# QIF.net
KiCad netlist of a schematic drawn in EAGLE
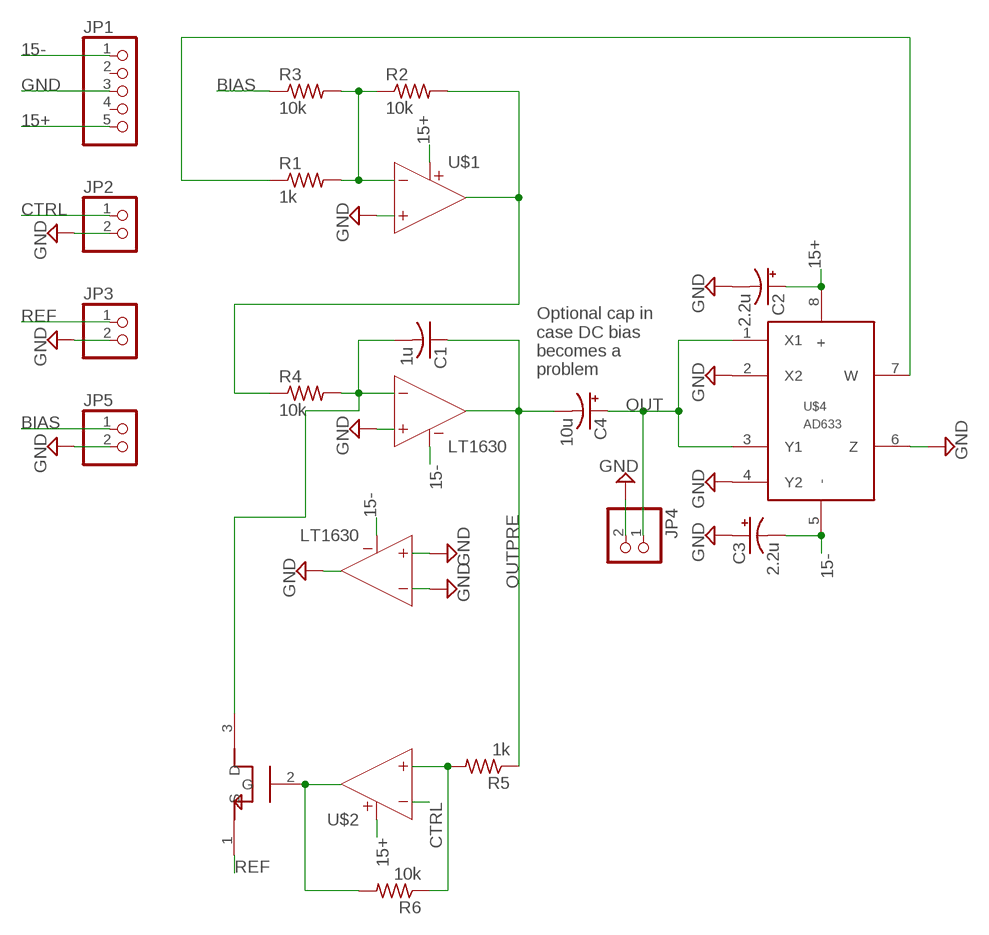
[diagram p0: schematic, sheet 1]

(export (version "E")
  (design (tool "Eeschema 10.0.6"))
  (components
    (comp (ref "C1")
      (value "1u")
      (footprint "eagle-import:C050-030X075")
      (libsource (lib "eagle-import") (part "C-US050-030X075"))
    )
    (comp (ref "C2")
      (value "2.2u")
      (footprint "eagle-import:E2,5-6E")
      (libsource (lib "eagle-import") (part "CPOL-USE2,5-6E"))
    )
    (comp (ref "C3")
      (value "2.2u")
      (footprint "eagle-import:E2,5-6E")
      (libsource (lib "eagle-import") (part "CPOL-USE2,5-6E"))
    )
    (comp (ref "C4")
      (value "10u")
      (footprint "eagle-import:E2,5-6")
      (libsource (lib "eagle-import") (part "CPOL-USE2.5-6"))
    )
    (comp (ref "JP1")
      (value "PINHD-1X5")
      (footprint "eagle-import:1X05")
      (libsource (lib "eagle-import") (part "PINHD-1X5"))
    )
    (comp (ref "JP2")
      (value "PINHD-1X2")
      (footprint "eagle-import:1X02")
      (libsource (lib "eagle-import") (part "PINHD-1X2"))
    )
    (comp (ref "JP3")
      (value "PINHD-1X2")
      (footprint "eagle-import:1X02")
      (libsource (lib "eagle-import") (part "PINHD-1X2"))
    )
    (comp (ref "JP4")
      (value "PINHD-1X2")
      (footprint "eagle-import:1X02")
      (libsource (lib "eagle-import") (part "PINHD-1X2"))
    )
    (comp (ref "JP5")
      (value "PINHD-1X2")
      (footprint "eagle-import:1X02")
      (libsource (lib "eagle-import") (part "PINHD-1X2"))
    )
    (comp (ref "R1")
      (value "1k")
      (footprint "eagle-import:0207_10")
      (libsource (lib "eagle-import") (part "R-US_0207/10"))
    )
    (comp (ref "R2")
      (value "10k")
      (footprint "eagle-import:0309V")
      (libsource (lib "eagle-import") (part "R-US_0309/V"))
    )
    (comp (ref "R3")
      (value "10k")
      (footprint "eagle-import:0207_10")
      (libsource (lib "eagle-import") (part "R-US_0207/10"))
    )
    (comp (ref "R4")
      (value "10k")
      (footprint "eagle-import:0207_10")
      (libsource (lib "eagle-import") (part "R-US_0207/10"))
    )
    (comp (ref "R5")
      (value "1k")
      (footprint "eagle-import:0207_10")
      (libsource (lib "eagle-import") (part "R-US_0207/10"))
    )
    (comp (ref "R6")
      (value "10k")
      (footprint "eagle-import:0309V")
      (libsource (lib "eagle-import") (part "R-US_0309/V"))
    )
    (comp (ref "U$1")
      (value "LT1630")
      (footprint "eagle-import:DIL8")
      (libsource (lib "eagle-import") (part "LT1630"))
    )
    (comp (ref "U$2")
      (value "LT1630")
      (footprint "eagle-import:DIL8")
      (libsource (lib "eagle-import") (part "LT1630"))
    )
    (comp (ref "U$3")
      (value "2N7000")
      (footprint "eagle-import:TO-92")
      (libsource (lib "eagle-import") (part "2N7000"))
    )
    (comp (ref "U$4")
      (value "AD633")
      (footprint "eagle-import:DIL8")
      (libsource (lib "eagle-import") (part "AD633"))
    )
  )
  (nets
    (net (code "1") (name "/15+") (class "Default")
      (node (ref "C2") (pin "+") (pinfunction "+_+") (pintype "passive"))
      (node (ref "JP1") (pin "5") (pinfunction "5_5") (pintype "passive"))
      (node (ref "U$1") (pin "8") (pinfunction "V+_8") (pintype "passive"))
      (node (ref "U$2") (pin "8") (pinfunction "V+_8") (pintype "passive"))
      (node (ref "U$4") (pin "8") (pinfunction "+_8") (pintype "bidirectional"))
    )
    (net (code "2") (name "/15-") (class "Default")
      (node (ref "C3") (pin "-") (pinfunction "-_-") (pintype "passive"))
      (node (ref "JP1") (pin "1") (pinfunction "1_1") (pintype "passive"))
      (node (ref "U$1") (pin "4") (pinfunction "V-_4") (pintype "passive"))
      (node (ref "U$2") (pin "4") (pinfunction "V-_4") (pintype "passive"))
      (node (ref "U$4") (pin "5") (pinfunction "-_5") (pintype "bidirectional"))
    )
    (net (code "3") (name "/BIAS") (class "Default")
      (node (ref "JP5") (pin "1") (pinfunction "1_1") (pintype "passive"))
      (node (ref "R3") (pin "1") (pinfunction "1_1") (pintype "passive"))
    )
    (net (code "4") (name "/CTRL") (class "Default")
      (node (ref "JP2") (pin "1") (pinfunction "1_1") (pintype "passive"))
      (node (ref "U$2") (pin "2") (pinfunction "IN-_2") (pintype "passive"))
    )
    (net (code "5") (name "/OUT") (class "Default")
      (node (ref "C4") (pin "+") (pinfunction "+_+") (pintype "passive"))
      (node (ref "JP4") (pin "1") (pinfunction "1_1") (pintype "passive"))
      (node (ref "U$4") (pin "1") (pinfunction "X1_1") (pintype "bidirectional"))
      (node (ref "U$4") (pin "3") (pinfunction "Y1_3") (pintype "bidirectional"))
    )
    (net (code "6") (name "/OUTPRE") (class "Default")
      (node (ref "C1") (pin "1") (pinfunction "1_1") (pintype "passive"))
      (node (ref "C4") (pin "-") (pinfunction "-_-") (pintype "passive"))
      (node (ref "R5") (pin "1") (pinfunction "1_1") (pintype "passive"))
      (node (ref "U$1") (pin "7") (pinfunction "OUT1_7") (pintype "passive"))
    )
    (net (code "7") (name "/REF") (class "Default")
      (node (ref "JP3") (pin "1") (pinfunction "1_1") (pintype "passive"))
      (node (ref "U$3") (pin "1") (pinfunction "S_1") (pintype "bidirectional"))
    )
    (net (code "8") (name "GND") (class "Default")
      (node (ref "C2") (pin "-") (pinfunction "-_-") (pintype "passive"))
      (node (ref "C3") (pin "+") (pinfunction "+_+") (pintype "passive"))
      (node (ref "JP1") (pin "3") (pinfunction "3_3") (pintype "passive"))
      (node (ref "JP2") (pin "2") (pinfunction "2_2") (pintype "passive"))
      (node (ref "JP3") (pin "2") (pinfunction "2_2") (pintype "passive"))
      (node (ref "JP4") (pin "2") (pinfunction "2_2") (pintype "passive"))
      (node (ref "JP5") (pin "2") (pinfunction "2_2") (pintype "passive"))
      (node (ref "U$1") (pin "3") (pinfunction "IN+_3") (pintype "passive"))
      (node (ref "U$1") (pin "5") (pinfunction "IN+1_5") (pintype "passive"))
      (node (ref "U$2") (pin "5") (pinfunction "IN+1_5") (pintype "passive"))
      (node (ref "U$2") (pin "6") (pinfunction "IN-1_6") (pintype "passive"))
      (node (ref "U$2") (pin "7") (pinfunction "OUT1_7") (pintype "passive"))
      (node (ref "U$4") (pin "2") (pinfunction "X2_2") (pintype "bidirectional"))
      (node (ref "U$4") (pin "4") (pinfunction "Y2_4") (pintype "bidirectional"))
      (node (ref "U$4") (pin "6") (pinfunction "Z_6") (pintype "bidirectional"))
    )
    (net (code "9") (name "Net-(U$1-IN-)") (class "Default")
      (node (ref "R1") (pin "2") (pinfunction "2_2") (pintype "passive"))
      (node (ref "R2") (pin "1") (pinfunction "1_1") (pintype "passive"))
      (node (ref "R3") (pin "2") (pinfunction "2_2") (pintype "passive"))
      (node (ref "U$1") (pin "2") (pinfunction "IN-_2") (pintype "passive"))
    )
    (net (code "10") (name "Net-(U$1-IN-1)") (class "Default")
      (node (ref "C1") (pin "2") (pinfunction "2_2") (pintype "passive"))
      (node (ref "R4") (pin "2") (pinfunction "2_2") (pintype "passive"))
      (node (ref "U$1") (pin "6") (pinfunction "IN-1_6") (pintype "passive"))
      (node (ref "U$3") (pin "3") (pinfunction "D_3") (pintype "bidirectional"))
    )
    (net (code "11") (name "Net-(U$1-OUT)") (class "Default")
      (node (ref "R2") (pin "2") (pinfunction "2_2") (pintype "passive"))
      (node (ref "R4") (pin "1") (pinfunction "1_1") (pintype "passive"))
      (node (ref "U$1") (pin "1") (pinfunction "OUT_1") (pintype "passive"))
    )
    (net (code "12") (name "Net-(U$2-IN+)") (class "Default")
      (node (ref "R5") (pin "2") (pinfunction "2_2") (pintype "passive"))
      (node (ref "R6") (pin "1") (pinfunction "1_1") (pintype "passive"))
      (node (ref "U$2") (pin "3") (pinfunction "IN+_3") (pintype "passive"))
    )
    (net (code "13") (name "Net-(U$2-OUT)") (class "Default")
      (node (ref "R6") (pin "2") (pinfunction "2_2") (pintype "passive"))
      (node (ref "U$2") (pin "1") (pinfunction "OUT_1") (pintype "passive"))
      (node (ref "U$3") (pin "2") (pinfunction "G_2") (pintype "bidirectional"))
    )
    (net (code "14") (name "Net-(U$4-W)") (class "Default")
      (node (ref "R1") (pin "1") (pinfunction "1_1") (pintype "passive"))
      (node (ref "U$4") (pin "7") (pinfunction "W_7") (pintype "bidirectional"))
    )
    (net (code "15") (name "unconnected-(JP1-Pad2)") (class "Default")
      (node (ref "JP1") (pin "2") (pinfunction "2_2") (pintype "passive"))
    )
    (net (code "16") (name "unconnected-(JP1-Pad4)") (class "Default")
      (node (ref "JP1") (pin "4") (pinfunction "4_4") (pintype "passive"))
    )
  )
)
